# lisa_mx_s_quad.net
KiCad netlist of a schematic drawn in Altium Designer
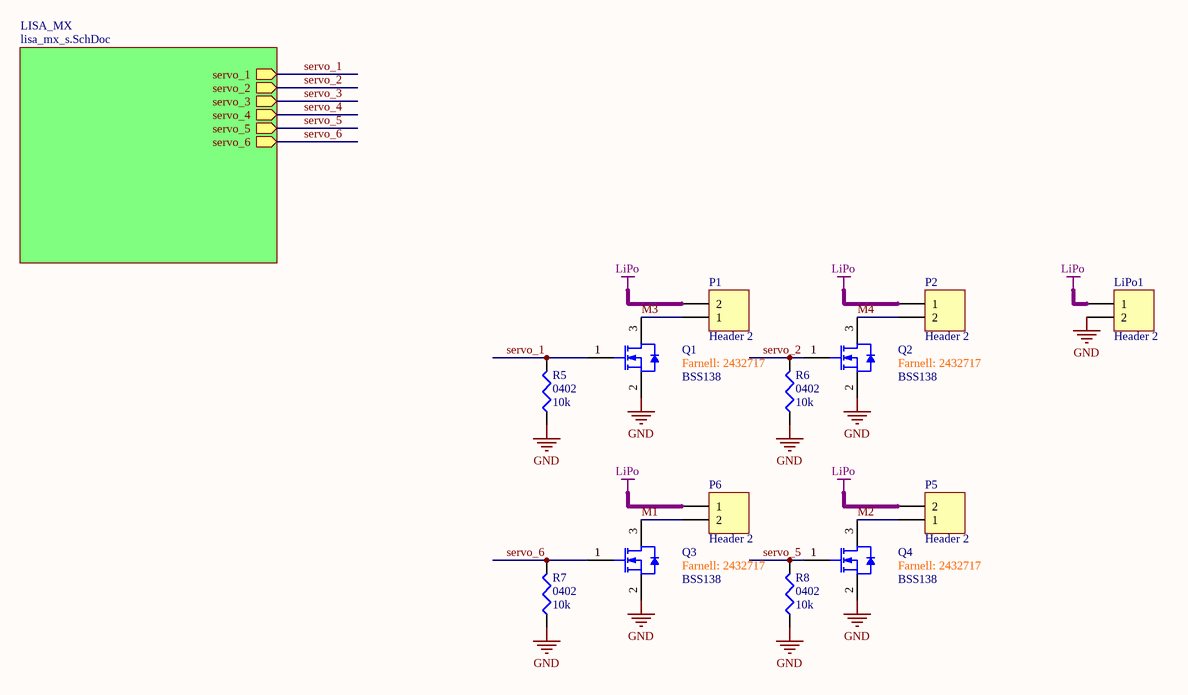
[diagram p0: lisa_mx_s_quad.SchDoc]

(export (version "E")
  (design (tool "Eeschema 10.0.6"))
  (components
    (comp (ref "LiPo1")
      (value "Header 2")
      (footprint "PICOBLADE_53047-0210")
      (description "Header, 2-Pin")
      (libsource (lib "") (part "Header 2_1"))
    )
    (comp (ref "P1")
      (value "Header 2")
      (footprint "PICOBLADE_53047-0210")
      (description "Header, 2-Pin")
      (libsource (lib "Miscellaneous Connectors") (part "Header 2"))
    )
    (comp (ref "P2")
      (value "Header 2")
      (footprint "PICOBLADE_53047-0210")
      (description "Header, 2-Pin")
      (libsource (lib "") (part "Header 2_1"))
    )
    (comp (ref "P5")
      (value "Header 2")
      (footprint "PICOBLADE_53047-0210")
      (description "Header, 2-Pin")
      (libsource (lib "Miscellaneous Connectors") (part "Header 2"))
    )
    (comp (ref "P6")
      (value "Header 2")
      (footprint "PICOBLADE_53047-0210")
      (description "Header, 2-Pin")
      (libsource (lib "") (part "Header 2_1"))
    )
    (comp (ref "Q1")
      (value "BSS138")
      (footprint "SOT23A_CDW")
      (fields (field (name "FARNELL") "2432717") (field (name "Comment") "N-FET"))
      (libsource (lib "CDW Misc") (part "BSS138"))
    )
    (comp (ref "Q2")
      (value "BSS138")
      (footprint "SOT23A_CDW")
      (fields (field (name "FARNELL") "2432717") (field (name "Comment") "N-FET"))
      (libsource (lib "CDW Misc") (part "BSS138"))
    )
    (comp (ref "Q3")
      (value "BSS138")
      (footprint "SOT23A_CDW")
      (fields (field (name "FARNELL") "2432717") (field (name "Comment") "N-FET"))
      (libsource (lib "CDW Misc") (part "BSS138"))
    )
    (comp (ref "Q4")
      (value "BSS138")
      (footprint "SOT23A_CDW")
      (fields (field (name "FARNELL") "2432717") (field (name "Comment") "N-FET"))
      (libsource (lib "CDW Misc") (part "BSS138"))
    )
    (comp (ref "R5")
      (value "0402")
      (footprint "V0402RES")
      (description "Resistor")
      (fields (field (name "ALTIUM_VALUE") "10k"))
      (libsource (lib "altium-import") (part "root_1_Res3_"))
    )
    (comp (ref "R6")
      (value "0402")
      (footprint "V0402RES")
      (description "Resistor")
      (fields (field (name "ALTIUM_VALUE") "10k"))
      (libsource (lib "altium-import") (part "root_1_Res3_"))
    )
    (comp (ref "R7")
      (value "0402")
      (footprint "V0402RES")
      (description "Resistor")
      (fields (field (name "ALTIUM_VALUE") "10k"))
      (libsource (lib "altium-import") (part "root_1_Res3_"))
    )
    (comp (ref "R8")
      (value "0402")
      (footprint "V0402RES")
      (description "Resistor")
      (fields (field (name "ALTIUM_VALUE") "10k"))
      (libsource (lib "altium-import") (part "root_1_Res3_"))
    )
  )
  (nets
    (net (code "1") (name "/M1") (class "Default")
      (node (ref "P6") (pin "2") (pinfunction "2_2") (pintype "passive"))
      (node (ref "Q3") (pin "3") (pinfunction "D_3") (pintype "passive"))
    )
    (net (code "2") (name "/M2") (class "Default")
      (node (ref "P5") (pin "1") (pinfunction "1_1") (pintype "passive"))
      (node (ref "Q4") (pin "3") (pinfunction "D_3") (pintype "passive"))
    )
    (net (code "3") (name "/M3") (class "Default")
      (node (ref "P1") (pin "1") (pinfunction "1_1") (pintype "passive"))
      (node (ref "Q1") (pin "3") (pinfunction "D_3") (pintype "passive"))
    )
    (net (code "4") (name "/M4") (class "Default")
      (node (ref "P2") (pin "2") (pinfunction "2_2") (pintype "passive"))
      (node (ref "Q2") (pin "3") (pinfunction "D_3") (pintype "passive"))
    )
    (net (code "5") (name "/servo_1") (class "Default")
      (node (ref "Q1") (pin "1") (pinfunction "G_1") (pintype "passive"))
      (node (ref "R5") (pin "2") (pinfunction "2_2") (pintype "passive"))
    )
    (net (code "6") (name "/servo_2") (class "Default")
      (node (ref "Q2") (pin "1") (pinfunction "G_1") (pintype "passive"))
      (node (ref "R6") (pin "2") (pinfunction "2_2") (pintype "passive"))
    )
    (net (code "9") (name "/servo_5") (class "Default")
      (node (ref "Q4") (pin "1") (pinfunction "G_1") (pintype "passive"))
      (node (ref "R8") (pin "2") (pinfunction "2_2") (pintype "passive"))
    )
    (net (code "10") (name "/servo_6") (class "Default")
      (node (ref "Q3") (pin "1") (pinfunction "G_1") (pintype "passive"))
      (node (ref "R7") (pin "2") (pinfunction "2_2") (pintype "passive"))
    )
    (net (code "11") (name "GND") (class "Default")
      (node (ref "LiPo1") (pin "2") (pinfunction "2_2") (pintype "passive"))
      (node (ref "Q1") (pin "2") (pinfunction "S_2") (pintype "passive"))
      (node (ref "Q2") (pin "2") (pinfunction "S_2") (pintype "passive"))
      (node (ref "Q3") (pin "2") (pinfunction "S_2") (pintype "passive"))
      (node (ref "Q4") (pin "2") (pinfunction "S_2") (pintype "passive"))
      (node (ref "R5") (pin "1") (pinfunction "1_1") (pintype "passive"))
      (node (ref "R6") (pin "1") (pinfunction "1_1") (pintype "passive"))
      (node (ref "R7") (pin "1") (pinfunction "1_1") (pintype "passive"))
      (node (ref "R8") (pin "1") (pinfunction "1_1") (pintype "passive"))
    )
    (net (code "12") (name "LiPo") (class "Default")
      (node (ref "LiPo1") (pin "1") (pinfunction "1_1") (pintype "passive"))
      (node (ref "P1") (pin "2") (pinfunction "2_2") (pintype "passive"))
      (node (ref "P2") (pin "1") (pinfunction "1_1") (pintype "passive"))
      (node (ref "P5") (pin "2") (pinfunction "2_2") (pintype "passive"))
      (node (ref "P6") (pin "1") (pinfunction "1_1") (pintype "passive"))
    )
  )
)
